# Pi-Go.net
KiCad netlist of a schematic drawn in EAGLE
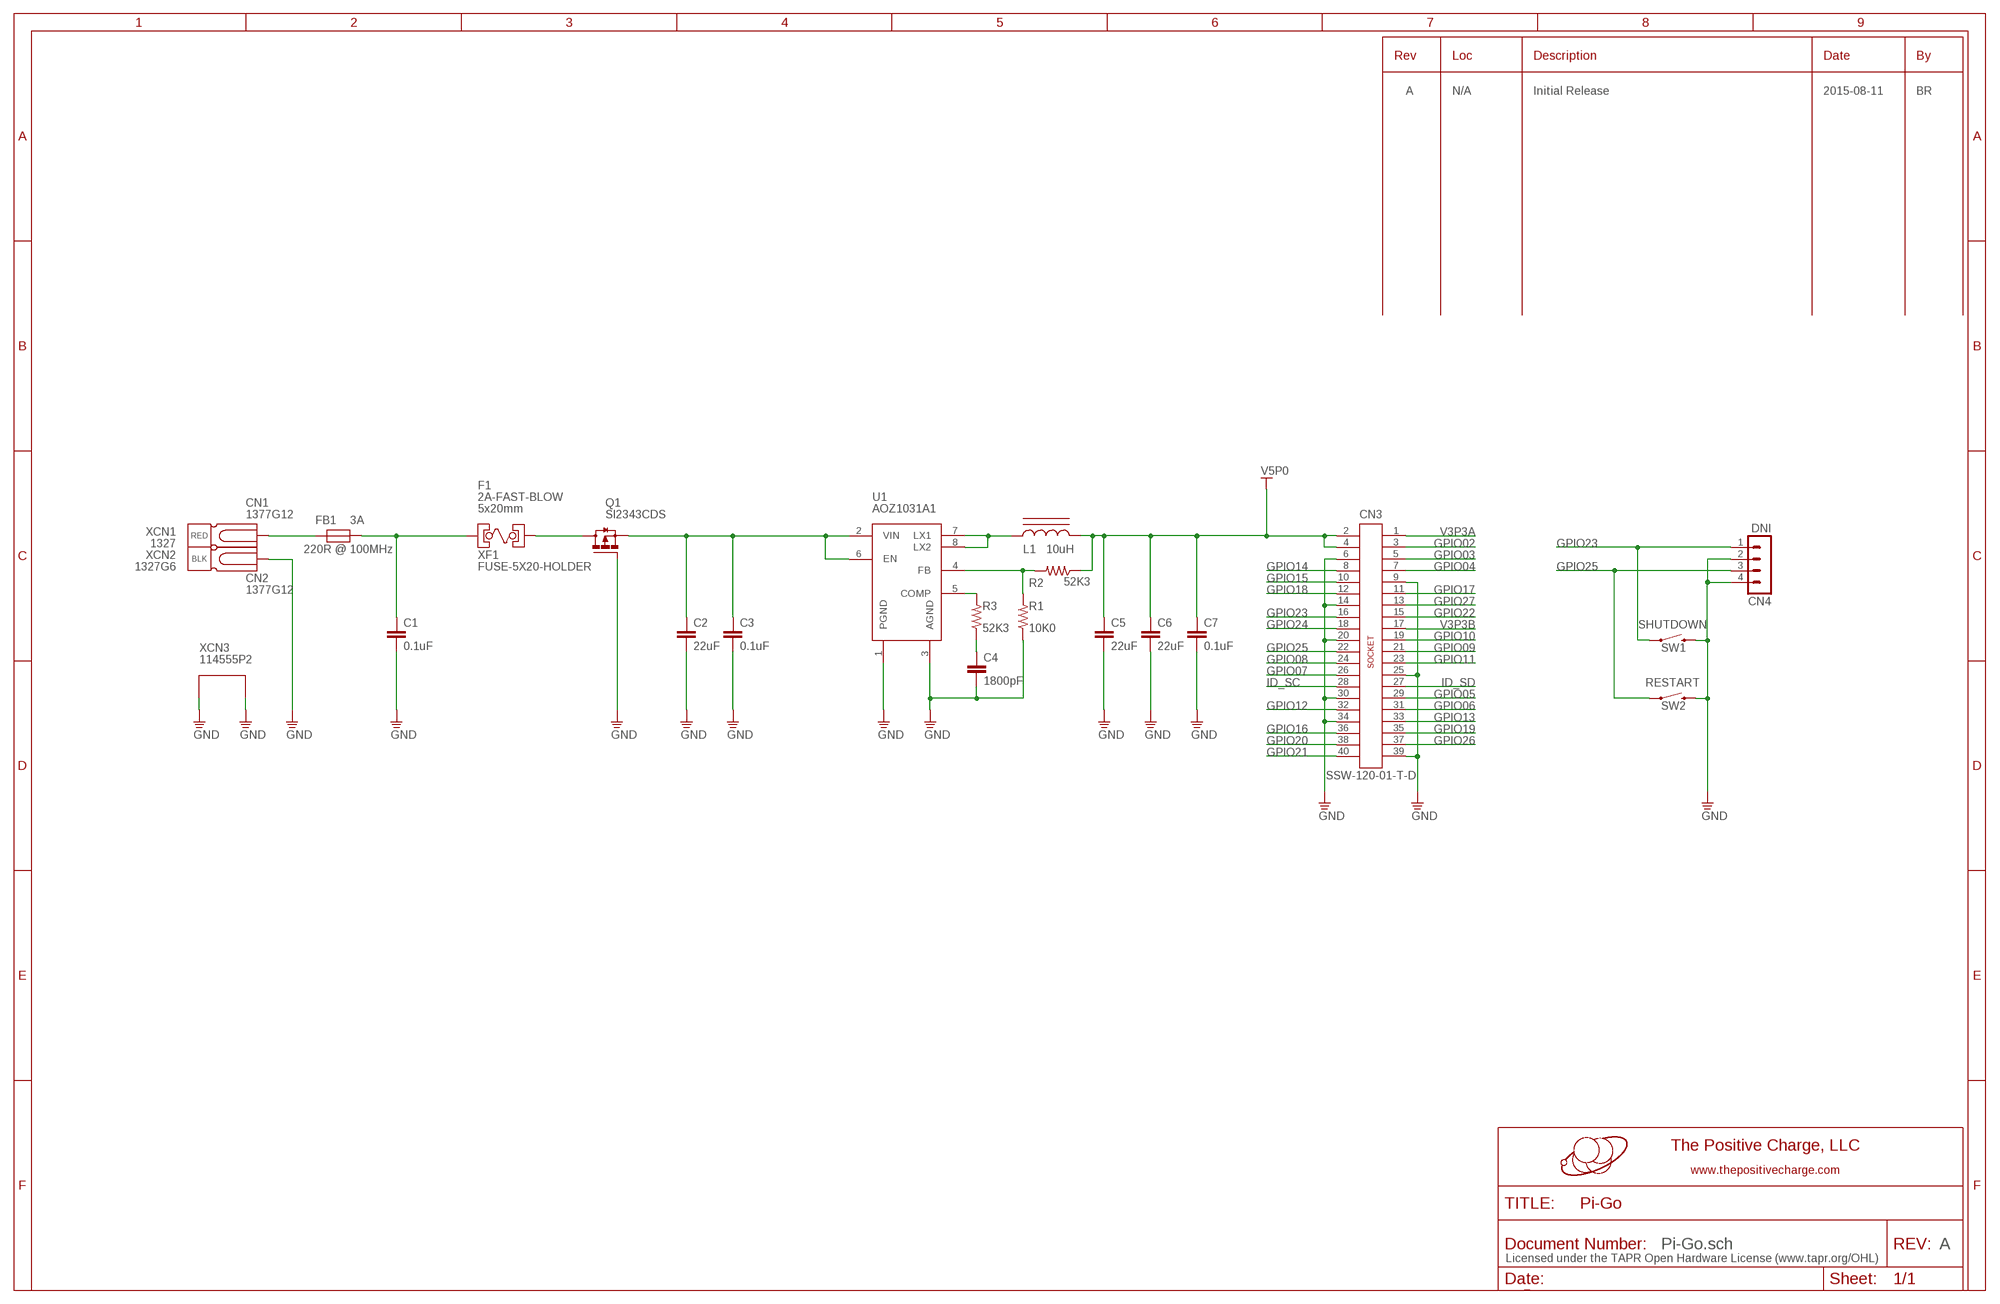
[diagram p0: schematic, sheet 1]

(export (version "E")
  (design (tool "Eeschema 10.0.6"))
  (components
    (comp (ref "C1")
      (value "0.1uF")
      (footprint "eagle-import:C0805")
      (libsource (lib "eagle-import") (part "C-EUC0805"))
    )
    (comp (ref "C2")
      (value "22uF")
      (footprint "eagle-import:C1210")
      (libsource (lib "eagle-import") (part "C-EUC1210"))
    )
    (comp (ref "C3")
      (value "0.1uF")
      (footprint "eagle-import:C0805")
      (libsource (lib "eagle-import") (part "C-EUC0805"))
    )
    (comp (ref "C4")
      (value "1800pF")
      (footprint "eagle-import:C0805")
      (libsource (lib "eagle-import") (part "C-EUC0805"))
    )
    (comp (ref "C5")
      (value "22uF")
      (footprint "eagle-import:C1210")
      (libsource (lib "eagle-import") (part "C-EUC1210"))
    )
    (comp (ref "C6")
      (value "22uF")
      (footprint "eagle-import:C1210")
      (libsource (lib "eagle-import") (part "C-EUC1210"))
    )
    (comp (ref "C7")
      (value "0.1uF")
      (footprint "eagle-import:C0805")
      (libsource (lib "eagle-import") (part "C-EUC0805"))
    )
    (comp (ref "CN1")
      (value "1377G12")
      (footprint "eagle-import:1377G12")
      (libsource (lib "eagle-import") (part "1377G12"))
    )
    (comp (ref "CN2")
      (value "1377G12")
      (footprint "eagle-import:1377G12")
      (libsource (lib "eagle-import") (part "1377G12"))
    )
    (comp (ref "CN3")
      (value "SSW-120-01-T-D")
      (footprint "eagle-import:SSW-120-XX-X-D")
      (libsource (lib "eagle-import") (part "SSW-120-01-T-D"))
    )
    (comp (ref "CN4")
      (value "DNI")
      (footprint "eagle-import:MA04-1")
      (libsource (lib "eagle-import") (part "MA04-1"))
    )
    (comp (ref "FB1")
      (value "3A")
      (footprint "eagle-import:C0805")
      (libsource (lib "eagle-import") (part "FB0805"))
    )
    (comp (ref "L1")
      (value "10uH")
      (footprint "eagle-import:POWER-INDUCTOR-SHIELD")
      (libsource (lib "eagle-import") (part "SRP1265A"))
    )
    (comp (ref "Q1")
      (value "SI2343CDS")
      (footprint "eagle-import:SOT23")
      (libsource (lib "eagle-import") (part "SI2343CDS"))
    )
    (comp (ref "R1")
      (value "10K0")
      (footprint "eagle-import:R0805")
      (libsource (lib "eagle-import") (part "R-US_R0805"))
    )
    (comp (ref "R2")
      (value "52K3")
      (footprint "eagle-import:R0805")
      (libsource (lib "eagle-import") (part "R-US_R0805"))
    )
    (comp (ref "R3")
      (value "52K3")
      (footprint "eagle-import:R0805")
      (libsource (lib "eagle-import") (part "R-US_R0805"))
    )
    (comp (ref "SW1")
      (value "SWITCH-MOMENTARY-2SMD-4")
      (footprint "eagle-import:TACTILE_SWITCH_TALL")
      (libsource (lib "eagle-import") (part "SWITCH-MOMENTARY-2SMD-4"))
    )
    (comp (ref "SW2")
      (value "SWITCH-MOMENTARY-2SMD-4")
      (footprint "eagle-import:TACTILE_SWITCH_TALL")
      (libsource (lib "eagle-import") (part "SWITCH-MOMENTARY-2SMD-4"))
    )
    (comp (ref "U1")
      (value "AOZ1031A1")
      (footprint "eagle-import:AOZ1031AI-SO08")
      (libsource (lib "eagle-import") (part "AOZ1031A1"))
    )
    (comp (ref "XCN3")
      (value "114555P2")
      (footprint "eagle-import:APP2X1CLIP")
      (libsource (lib "eagle-import") (part "114555P2"))
    )
    (comp (ref "XF1")
      (value "FUSE-5X20-HOLDER")
      (footprint "eagle-import:LITTELFUSE-02540101Z")
      (libsource (lib "eagle-import") (part "FUSE-5X20-HOLDER"))
    )
  )
  (nets
    (net (code "1") (name "/GPIO02") (class "Default")
      (node (ref "CN3") (pin "3") (pinfunction "3_3") (pintype "passive"))
    )
    (net (code "2") (name "/GPIO03") (class "Default")
      (node (ref "CN3") (pin "5") (pinfunction "5_5") (pintype "passive"))
    )
    (net (code "3") (name "/GPIO04") (class "Default")
      (node (ref "CN3") (pin "7") (pinfunction "7_7") (pintype "passive"))
    )
    (net (code "4") (name "/GPIO05") (class "Default")
      (node (ref "CN3") (pin "29") (pinfunction "29_29") (pintype "passive"))
    )
    (net (code "5") (name "/GPIO06") (class "Default")
      (node (ref "CN3") (pin "31") (pinfunction "31_31") (pintype "passive"))
    )
    (net (code "6") (name "/GPIO07") (class "Default")
      (node (ref "CN3") (pin "26") (pinfunction "26_26") (pintype "passive"))
    )
    (net (code "7") (name "/GPIO08") (class "Default")
      (node (ref "CN3") (pin "24") (pinfunction "24_24") (pintype "passive"))
    )
    (net (code "8") (name "/GPIO09") (class "Default")
      (node (ref "CN3") (pin "21") (pinfunction "21_21") (pintype "passive"))
    )
    (net (code "9") (name "/GPIO10") (class "Default")
      (node (ref "CN3") (pin "19") (pinfunction "19_19") (pintype "passive"))
    )
    (net (code "10") (name "/GPIO11") (class "Default")
      (node (ref "CN3") (pin "23") (pinfunction "23_23") (pintype "passive"))
    )
    (net (code "11") (name "/GPIO12") (class "Default")
      (node (ref "CN3") (pin "32") (pinfunction "32_32") (pintype "passive"))
    )
    (net (code "12") (name "/GPIO13") (class "Default")
      (node (ref "CN3") (pin "33") (pinfunction "33_33") (pintype "passive"))
    )
    (net (code "13") (name "/GPIO14") (class "Default")
      (node (ref "CN3") (pin "8") (pinfunction "8_8") (pintype "passive"))
    )
    (net (code "14") (name "/GPIO15") (class "Default")
      (node (ref "CN3") (pin "10") (pinfunction "10_10") (pintype "passive"))
    )
    (net (code "15") (name "/GPIO16") (class "Default")
      (node (ref "CN3") (pin "36") (pinfunction "36_36") (pintype "passive"))
    )
    (net (code "16") (name "/GPIO17") (class "Default")
      (node (ref "CN3") (pin "11") (pinfunction "11_11") (pintype "passive"))
    )
    (net (code "17") (name "/GPIO18") (class "Default")
      (node (ref "CN3") (pin "12") (pinfunction "12_12") (pintype "passive"))
    )
    (net (code "18") (name "/GPIO19") (class "Default")
      (node (ref "CN3") (pin "35") (pinfunction "35_35") (pintype "passive"))
    )
    (net (code "19") (name "/GPIO20") (class "Default")
      (node (ref "CN3") (pin "38") (pinfunction "38_38") (pintype "passive"))
    )
    (net (code "20") (name "/GPIO21") (class "Default")
      (node (ref "CN3") (pin "40") (pinfunction "40_40") (pintype "passive"))
    )
    (net (code "21") (name "/GPIO22") (class "Default")
      (node (ref "CN3") (pin "15") (pinfunction "15_15") (pintype "passive"))
    )
    (net (code "22") (name "/GPIO23") (class "Default")
      (node (ref "CN3") (pin "16") (pinfunction "16_16") (pintype "passive"))
      (node (ref "CN4") (pin "1") (pinfunction "1_1") (pintype "passive"))
      (node (ref "SW1") (pin "A1") (pinfunction "1_A1") (pintype "passive"))
      (node (ref "SW1") (pin "A2") (pinfunction "1_A2") (pintype "passive"))
    )
    (net (code "23") (name "/GPIO24") (class "Default")
      (node (ref "CN3") (pin "18") (pinfunction "18_18") (pintype "passive"))
    )
    (net (code "24") (name "/GPIO25") (class "Default")
      (node (ref "CN3") (pin "22") (pinfunction "22_22") (pintype "passive"))
      (node (ref "CN4") (pin "3") (pinfunction "3_3") (pintype "passive"))
      (node (ref "SW2") (pin "A1") (pinfunction "1_A1") (pintype "passive"))
      (node (ref "SW2") (pin "A2") (pinfunction "1_A2") (pintype "passive"))
    )
    (net (code "25") (name "/GPIO26") (class "Default")
      (node (ref "CN3") (pin "37") (pinfunction "37_37") (pintype "passive"))
    )
    (net (code "26") (name "/GPIO27") (class "Default")
      (node (ref "CN3") (pin "13") (pinfunction "13_13") (pintype "passive"))
    )
    (net (code "27") (name "/ID_SC") (class "Default")
      (node (ref "CN3") (pin "28") (pinfunction "28_28") (pintype "passive"))
    )
    (net (code "28") (name "/ID_SD") (class "Default")
      (node (ref "CN3") (pin "27") (pinfunction "27_27") (pintype "passive"))
    )
    (net (code "29") (name "/V3P3A") (class "Default")
      (node (ref "CN3") (pin "1") (pinfunction "1_1") (pintype "passive"))
    )
    (net (code "30") (name "/V3P3B") (class "Default")
      (node (ref "CN3") (pin "17") (pinfunction "17_17") (pintype "passive"))
    )
    (net (code "31") (name "GND") (class "Default")
      (node (ref "C1") (pin "2") (pinfunction "2_2") (pintype "passive"))
      (node (ref "C2") (pin "2") (pinfunction "2_2") (pintype "passive"))
      (node (ref "C3") (pin "2") (pinfunction "2_2") (pintype "passive"))
      (node (ref "C4") (pin "2") (pinfunction "2_2") (pintype "passive"))
      (node (ref "C5") (pin "2") (pinfunction "2_2") (pintype "passive"))
      (node (ref "C6") (pin "2") (pinfunction "2_2") (pintype "passive"))
      (node (ref "C7") (pin "2") (pinfunction "2_2") (pintype "passive"))
      (node (ref "CN2") (pin "P$1") (pinfunction "P$1_P$1") (pintype "passive"))
      (node (ref "CN3") (pin "14") (pinfunction "14_14") (pintype "passive"))
      (node (ref "CN3") (pin "20") (pinfunction "20_20") (pintype "passive"))
      (node (ref "CN3") (pin "25") (pinfunction "25_25") (pintype "passive"))
      (node (ref "CN3") (pin "30") (pinfunction "30_30") (pintype "passive"))
      (node (ref "CN3") (pin "34") (pinfunction "34_34") (pintype "passive"))
      (node (ref "CN3") (pin "39") (pinfunction "39_39") (pintype "passive"))
      (node (ref "CN3") (pin "6") (pinfunction "6_6") (pintype "passive"))
      (node (ref "CN3") (pin "9") (pinfunction "9_9") (pintype "passive"))
      (node (ref "CN4") (pin "2") (pinfunction "2_2") (pintype "passive"))
      (node (ref "CN4") (pin "4") (pinfunction "4_4") (pintype "passive"))
      (node (ref "Q1") (pin "1") (pinfunction "G_1") (pintype "passive"))
      (node (ref "R1") (pin "1") (pinfunction "1_1") (pintype "passive"))
      (node (ref "SW1") (pin "B1") (pinfunction "2_B1") (pintype "passive"))
      (node (ref "SW1") (pin "B2") (pinfunction "2_B2") (pintype "passive"))
      (node (ref "SW2") (pin "B1") (pinfunction "2_B1") (pintype "passive"))
      (node (ref "SW2") (pin "B2") (pinfunction "2_B2") (pintype "passive"))
      (node (ref "U1") (pin "1") (pinfunction "PGND_1") (pintype "bidirectional"))
      (node (ref "U1") (pin "3") (pinfunction "AGND_3") (pintype "power_in"))
      (node (ref "XCN3") (pin "P$1") (pinfunction "1_P$1") (pintype "passive"))
      (node (ref "XCN3") (pin "P$2") (pinfunction "2_P$2") (pintype "passive"))
    )
    (net (code "32") (name "Net-(C4-Pad1)") (class "Default")
      (node (ref "C4") (pin "1") (pinfunction "1_1") (pintype "passive"))
      (node (ref "R3") (pin "1") (pinfunction "1_1") (pintype "passive"))
    )
    (net (code "33") (name "Net-(FB1-P$1)") (class "Default")
      (node (ref "CN1") (pin "P$1") (pinfunction "P$1_P$1") (pintype "passive"))
      (node (ref "FB1") (pin "1") (pinfunction "P$1_1") (pintype "passive"))
    )
    (net (code "34") (name "Net-(FB1-P$2)") (class "Default")
      (node (ref "C1") (pin "1") (pinfunction "1_1") (pintype "passive"))
      (node (ref "FB1") (pin "2") (pinfunction "P$2_2") (pintype "passive"))
      (node (ref "XF1") (pin "1") (pinfunction "P$1_1") (pintype "passive"))
    )
    (net (code "35") (name "Net-(Q1-D)") (class "Default")
      (node (ref "Q1") (pin "3") (pinfunction "D_3") (pintype "passive"))
      (node (ref "XF1") (pin "2") (pinfunction "P$2_2") (pintype "passive"))
    )
    (net (code "36") (name "Net-(Q1-S)") (class "Default")
      (node (ref "C2") (pin "1") (pinfunction "1_1") (pintype "passive"))
      (node (ref "C3") (pin "1") (pinfunction "1_1") (pintype "passive"))
      (node (ref "Q1") (pin "2") (pinfunction "S_2") (pintype "passive"))
      (node (ref "U1") (pin "2") (pinfunction "VIN_2") (pintype "power_in"))
      (node (ref "U1") (pin "6") (pinfunction "EN_6") (pintype "input"))
    )
    (net (code "37") (name "Net-(U1-COMP)") (class "Default")
      (node (ref "R3") (pin "2") (pinfunction "2_2") (pintype "passive"))
      (node (ref "U1") (pin "5") (pinfunction "COMP_5") (pintype "passive"))
    )
    (net (code "38") (name "Net-(U1-FB)") (class "Default")
      (node (ref "R1") (pin "2") (pinfunction "2_2") (pintype "passive"))
      (node (ref "R2") (pin "2") (pinfunction "2_2") (pintype "passive"))
      (node (ref "U1") (pin "4") (pinfunction "FB_4") (pintype "bidirectional"))
    )
    (net (code "39") (name "Net-(U1-LX1)") (class "Default")
      (node (ref "L1") (pin "1") (pinfunction "1_1") (pintype "passive"))
      (node (ref "U1") (pin "7") (pinfunction "LX1_7") (pintype "bidirectional"))
      (node (ref "U1") (pin "8") (pinfunction "LX2_8") (pintype "bidirectional"))
    )
    (net (code "40") (name "V5P0") (class "Default")
      (node (ref "C5") (pin "1") (pinfunction "1_1") (pintype "passive"))
      (node (ref "C6") (pin "1") (pinfunction "1_1") (pintype "passive"))
      (node (ref "C7") (pin "1") (pinfunction "1_1") (pintype "passive"))
      (node (ref "CN3") (pin "2") (pinfunction "2_2") (pintype "passive"))
      (node (ref "CN3") (pin "4") (pinfunction "4_4") (pintype "passive"))
      (node (ref "L1") (pin "2") (pinfunction "2_2") (pintype "passive"))
      (node (ref "R2") (pin "1") (pinfunction "1_1") (pintype "passive"))
    )
  )
)
